# WIFI.net
KiCad netlist of a schematic drawn in Altium Designer
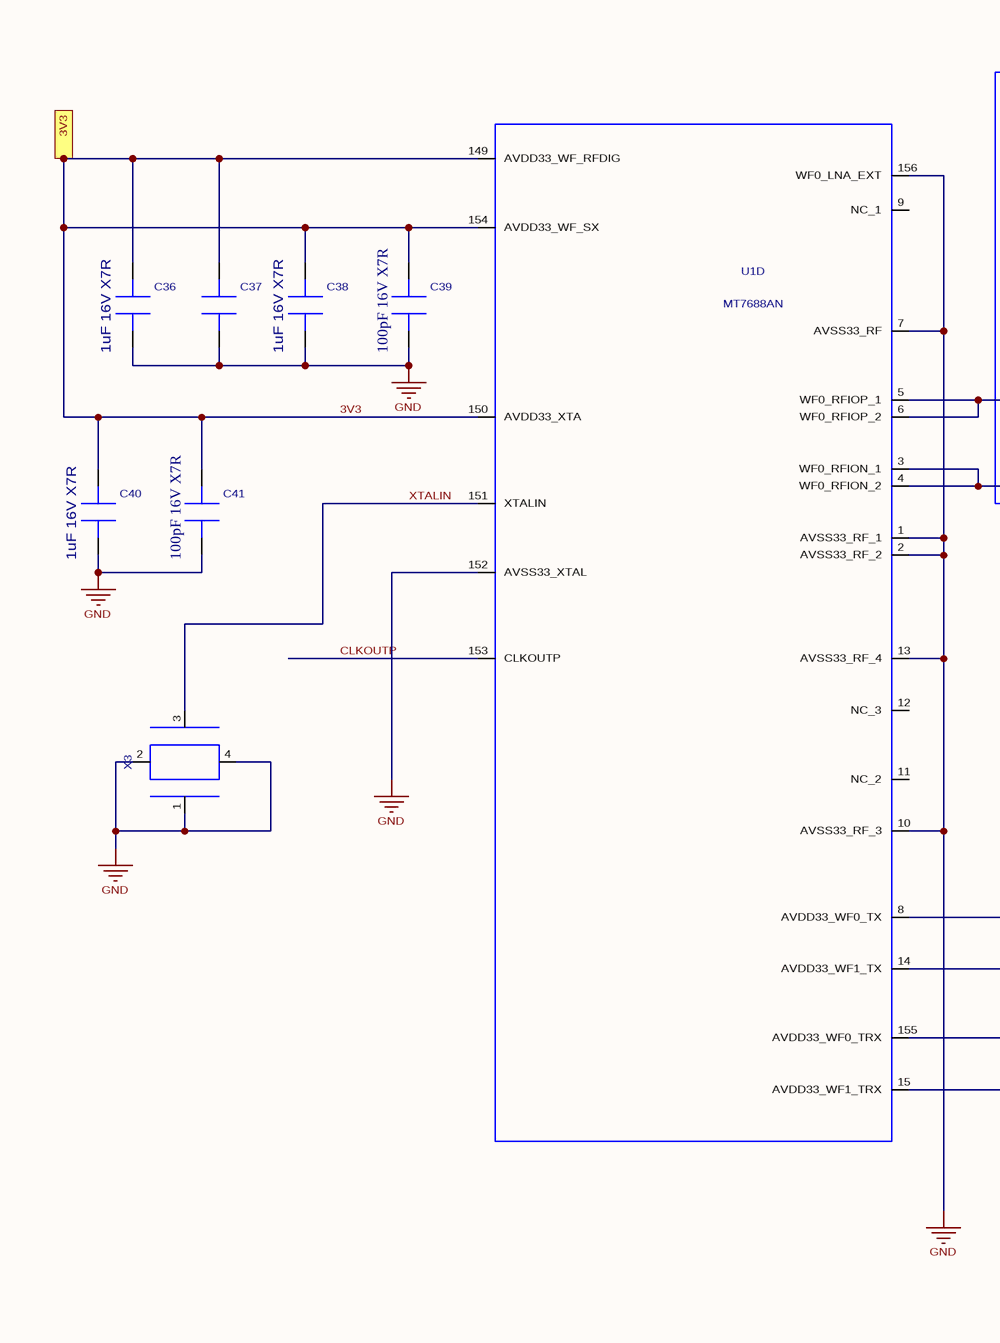
[diagram p0: WIFI.SchDoc, left]
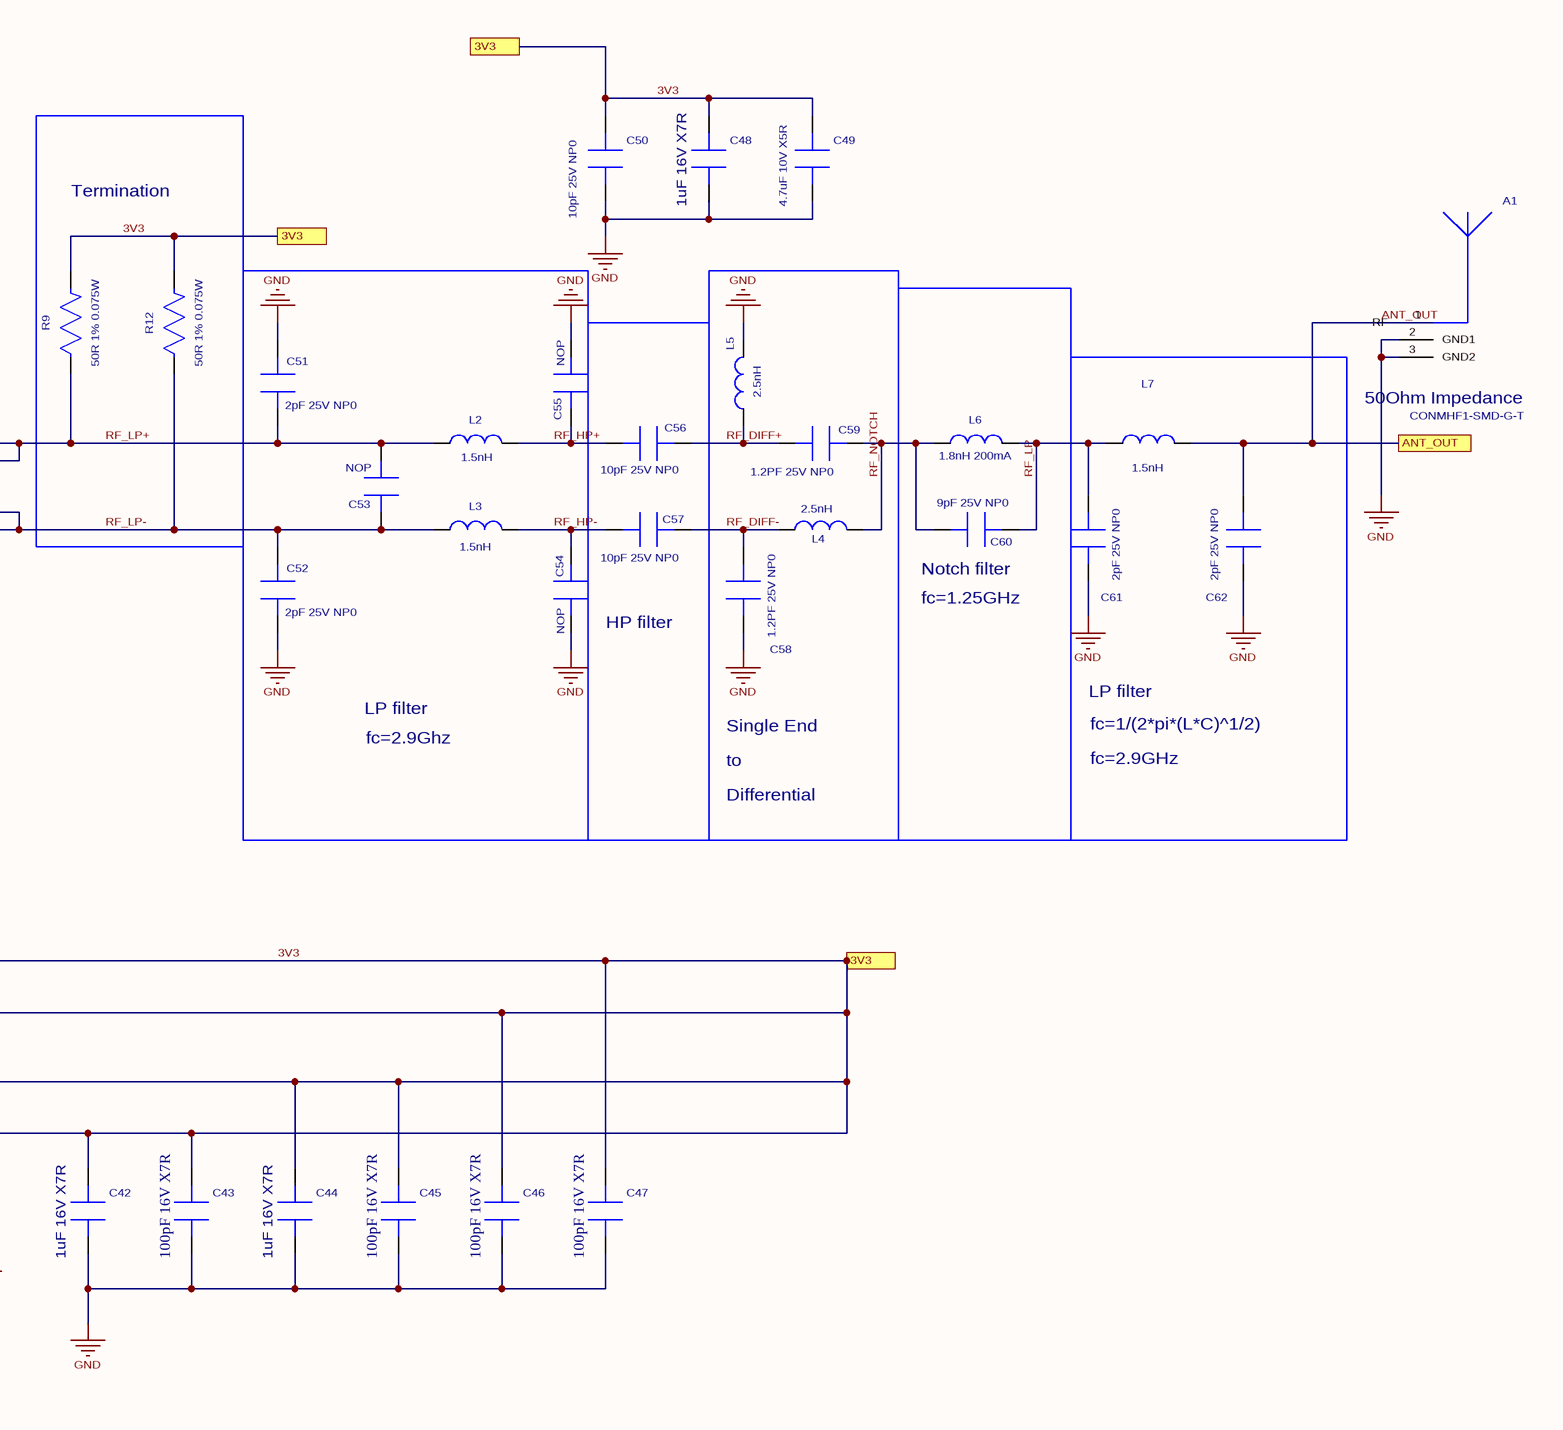
[diagram p1: WIFI.SchDoc, right]

(export (version "E")
  (design (tool "Eeschema 10.0.6"))
  (components
    (comp (ref "A1")
      (value "CONMHF1-SMD-G-T")
      (footprint "CONMHF1-SMD-G-T")
      (description "CONN UMC JACK STR SMD")
      (fields (field (name "MANUFACTURER") "Linx Technologies Inc."))
      (libsource (lib "*") (part "CONMHF1-SMD-G-T"))
    )
    (comp (ref "C36")
      (value "1uF 16V X7R")
      (footprint "C0402")
      (description "CAP CER 1UF 6.3V X7R 0402")
      (fields
        (field (name "PART NUMBER") "GRM155R70J105KA12D")
        (field (name "MANUFACTURER") "Murata Electronics")
      )
      (libsource (lib "NetworkModule") (part "CAP0402-105-6.3V-X7R"))
    )
    (comp (ref "C37")
      (value "CAP0201-101-16V-X7R")
      (footprint "C0201")
      (description "CAP CER 100PF 16V X7R 0201")
      (fields
        (field (name "PART NUMBER") "0201B101K160CT")
        (field (name "MANUFACTURER") "Walsin Technology Corporation")
      )
      (libsource (lib "NetworkModule") (part "CAP0201-101-16V-X7R"))
    )
    (comp (ref "C38")
      (value "1uF 16V X7R")
      (footprint "C0402")
      (description "CAP CER 1UF 6.3V X7R 0402")
      (fields
        (field (name "PART NUMBER") "GRM155R70J105KA12D")
        (field (name "MANUFACTURER") "Murata Electronics")
      )
      (libsource (lib "NetworkModule") (part "CAP0402-105-6.3V-X7R"))
    )
    (comp (ref "C39")
      (value "100pF 16V X7R")
      (footprint "C0201")
      (description "CAP CER 100PF 16V X7R 0201")
      (fields
        (field (name "PART NUMBER") "0201B101K160CT")
        (field (name "MANUFACTURER") "Walsin Technology Corporation")
      )
      (libsource (lib "NetworkModule") (part "CAP0201-101-16V-X7R"))
    )
    (comp (ref "C40")
      (value "1uF 16V X7R")
      (footprint "C0402")
      (description "CAP CER 1UF 6.3V X7R 0402")
      (fields
        (field (name "PART NUMBER") "GRM155R70J105KA12D")
        (field (name "MANUFACTURER") "Murata Electronics")
      )
      (libsource (lib "NetworkModule") (part "CAP0402-105-6.3V-X7R"))
    )
    (comp (ref "C41")
      (value "100pF 16V X7R")
      (footprint "C0201")
      (description "CAP CER 100PF 16V X7R 0201")
      (fields
        (field (name "PART NUMBER") "0201B101K160CT")
        (field (name "MANUFACTURER") "Walsin Technology Corporation")
      )
      (libsource (lib "NetworkModule") (part "CAP0201-101-16V-X7R"))
    )
    (comp (ref "C42")
      (value "1uF 16V X7R")
      (footprint "C0402")
      (description "CAP CER 1UF 6.3V X7R 0402")
      (fields
        (field (name "PART NUMBER") "GRM155R70J105KA12D")
        (field (name "MANUFACTURER") "Murata Electronics")
      )
      (libsource (lib "NetworkModule") (part "CAP0402-105-6.3V-X7R"))
    )
    (comp (ref "C43")
      (value "100pF 16V X7R")
      (footprint "C0201")
      (description "CAP CER 100PF 16V X7R 0201")
      (fields
        (field (name "PART NUMBER") "0201B101K160CT")
        (field (name "MANUFACTURER") "Walsin Technology Corporation")
      )
      (libsource (lib "NetworkModule") (part "CAP0201-101-16V-X7R"))
    )
    (comp (ref "C44")
      (value "1uF 16V X7R")
      (footprint "C0402")
      (description "CAP CER 1UF 6.3V X7R 0402")
      (fields
        (field (name "PART NUMBER") "GRM155R70J105KA12D")
        (field (name "MANUFACTURER") "Murata Electronics")
      )
      (libsource (lib "NetworkModule") (part "CAP0402-105-6.3V-X7R"))
    )
    (comp (ref "C45")
      (value "100pF 16V X7R")
      (footprint "C0201")
      (description "CAP CER 100PF 16V X7R 0201")
      (fields
        (field (name "PART NUMBER") "0201B101K160CT")
        (field (name "MANUFACTURER") "Walsin Technology Corporation")
      )
      (libsource (lib "NetworkModule") (part "CAP0201-101-16V-X7R"))
    )
    (comp (ref "C46")
      (value "100pF 16V X7R")
      (footprint "C0201")
      (description "CAP CER 100PF 16V X7R 0201")
      (fields
        (field (name "PART NUMBER") "0201B101K160CT")
        (field (name "MANUFACTURER") "Walsin Technology Corporation")
      )
      (libsource (lib "NetworkModule") (part "CAP0201-101-16V-X7R"))
    )
    (comp (ref "C47")
      (value "100pF 16V X7R")
      (footprint "C0201")
      (description "CAP CER 100PF 16V X7R 0201")
      (fields
        (field (name "PART NUMBER") "0201B101K160CT")
        (field (name "MANUFACTURER") "Walsin Technology Corporation")
      )
      (libsource (lib "NetworkModule") (part "CAP0201-101-16V-X7R"))
    )
    (comp (ref "C48")
      (value "1uF 16V X7R")
      (footprint "C0402")
      (description "CAP CER 1UF 6.3V X7R 0402")
      (fields
        (field (name "PART NUMBER") "GRM155R70J105KA12D")
        (field (name "MANUFACTURER") "Murata Electronics")
      )
      (libsource (lib "NetworkModule") (part "CAP0402-105-6.3V-X7R"))
    )
    (comp (ref "C49")
      (value "4.7uF 10V X5R")
      (footprint "C0402")
      (description "CAP CER 4.7UF 10V X5R 0402")
      (fields
        (field (name "PART NUMBER") "CL05A475MP5NRNC")
        (field (name "MANUFACTURER") "Samsung Electro-Mechanics")
      )
      (libsource (lib "NetworkModule") (part "CAP0402-475-10V-X5R"))
    )
    (comp (ref "C50")
      (value "10pF 25V NP0")
      (footprint "C0201")
      (description "CAP CER 10PF 25V C0G/NP0 0201")
      (fields
        (field (name "PART NUMBER") "0201N100J250CT")
        (field (name "MANUFACTURER") "Walsin Technology Corporation")
      )
      (libsource (lib "NetworkModule") (part "CAP0201-100-25V-NP0"))
    )
    (comp (ref "C51")
      (value "2pF 25V NP0")
      (footprint "C0201")
      (description "CAP CER 2PF 25V C0G/NP0 0201")
      (fields
        (field (name "PART NUMBER") "CL03C020BA3GNNC")
        (field (name "MANUFACTURER") "Samsung Electro-Mechanics")
      )
      (libsource (lib "NetworkModule") (part "CAP0201-020-25V-NP0"))
    )
    (comp (ref "C52")
      (value "2pF 25V NP0")
      (footprint "C0201")
      (description "CAP CER 2PF 25V C0G/NP0 0201")
      (fields
        (field (name "PART NUMBER") "CL03C020BA3GNNC")
        (field (name "MANUFACTURER") "Samsung Electro-Mechanics")
      )
      (libsource (lib "NetworkModule") (part "CAP0201-020-25V-NP0"))
    )
    (comp (ref "C53")
      (value "NOP")
      (footprint "C0201_NOP")
      (fields (field (name "Comment") "CAP0201-NOP"))
      (libsource (lib "NetworkModule") (part "CAP0201-NOP"))
    )
    (comp (ref "C54")
      (value "NOP")
      (footprint "C0201_NOP")
      (fields (field (name "Comment") "CAP0201-NOP"))
      (libsource (lib "NetworkModule") (part "CAP0201-NOP"))
    )
    (comp (ref "C55")
      (value "NOP")
      (footprint "C0201_NOP")
      (fields (field (name "Comment") "CAP0201-NOP"))
      (libsource (lib "NetworkModule") (part "CAP0201-NOP"))
    )
    (comp (ref "C56")
      (value "10pF 25V NP0")
      (footprint "C0201")
      (description "CAP CER 10PF 25V C0G/NP0 0201")
      (fields
        (field (name "PART NUMBER") "0201N100J250CT")
        (field (name "MANUFACTURER") "Walsin Technology Corporation")
      )
      (libsource (lib "NetworkModule") (part "CAP0201-100-25V-NP0"))
    )
    (comp (ref "C57")
      (value "10pF 25V NP0")
      (footprint "C0201")
      (description "CAP CER 10PF 25V C0G/NP0 0201")
      (fields
        (field (name "PART NUMBER") "0201N100J250CT")
        (field (name "MANUFACTURER") "Walsin Technology Corporation")
      )
      (libsource (lib "NetworkModule") (part "CAP0201-100-25V-NP0"))
    )
    (comp (ref "C58")
      (value "1.2PF 25V NP0")
      (footprint "C0201")
      (description "CAP CER 1.2PF 25V C0G/NP0 0201")
      (fields
        (field (name "PART NUMBER") "GRM0335C1E1R2WA01D")
        (field (name "MANUFACTURER") "Murata Electronics")
      )
      (libsource (lib "NetworkModule") (part "CAP0201-1R2-25V-NP0"))
    )
    (comp (ref "C59")
      (value "1.2PF 25V NP0")
      (footprint "C0201")
      (description "CAP CER 1.2PF 25V C0G/NP0 0201")
      (fields
        (field (name "PART NUMBER") "GRM0335C1E1R2WA01D")
        (field (name "MANUFACTURER") "Murata Electronics")
      )
      (libsource (lib "NetworkModule") (part "CAP0201-1R2-25V-NP0"))
    )
    (comp (ref "C60")
      (value "9pF 25V NP0")
      (footprint "C0201")
      (description "CAP CER 9PF 25V C0G 0201")
      (fields
        (field (name "PART NUMBER") "CGA1A2C0G1E090D030BA")
        (field (name "MANUFACTURER") "TDK Corporation")
      )
      (libsource (lib "NetworkModule") (part "CAP0201-090-100V-NP0"))
    )
    (comp (ref "C61")
      (value "2pF 25V NP0")
      (footprint "C0201")
      (description "CAP CER 2PF 25V C0G/NP0 0201")
      (fields
        (field (name "PART NUMBER") "CL03C020BA3GNNC")
        (field (name "MANUFACTURER") "Samsung Electro-Mechanics")
      )
      (libsource (lib "NetworkModule") (part "CAP0201-020-25V-NP0"))
    )
    (comp (ref "C62")
      (value "2pF 25V NP0")
      (footprint "C0201")
      (description "CAP CER 2PF 25V C0G/NP0 0201")
      (fields
        (field (name "PART NUMBER") "CL03C020BA3GNNC")
        (field (name "MANUFACTURER") "Samsung Electro-Mechanics")
      )
      (libsource (lib "NetworkModule") (part "CAP0201-020-25V-NP0"))
    )
    (comp (ref "L2")
      (value "1.5nH")
      (footprint "L0201")
      (description "INDUCTOR FIXED 1.5NH 0201")
      (fields
        (field (name "PART NUMBER") "WLCM0603TGB1N5TB")
        (field (name "MANUFACTURER") "Walsin Technology Corporation")
      )
      (libsource (lib "NetworkModule") (part "IND0201_1.5N_600MA"))
    )
    (comp (ref "L3")
      (value "1.5nH")
      (footprint "L0201")
      (description "INDUCTOR FIXED 1.5NH 0201")
      (fields
        (field (name "PART NUMBER") "WLCM0603TGB1N5TB")
        (field (name "MANUFACTURER") "Walsin Technology Corporation")
      )
      (libsource (lib "NetworkModule") (part "IND0201_1.5N_600MA"))
    )
    (comp (ref "L4")
      (value "2.5nH")
      (footprint "L0201")
      (description "FIXED IND 2.5NH 500MA 200MOHM SM")
      (fields
        (field (name "PART NUMBER") "LQP03TN2N5B02D")
        (field (name "MANUFACTURER") "Murata Electronics")
      )
      (libsource (lib "NetworkModule") (part "IND0201_2.5N_500MA"))
    )
    (comp (ref "L5")
      (value "2.5nH")
      (footprint "L0201")
      (description "FIXED IND 2.5NH 500MA 200MOHM SM")
      (fields
        (field (name "PART NUMBER") "LQP03TN2N5B02D")
        (field (name "MANUFACTURER") "Murata Electronics")
      )
      (libsource (lib "NetworkModule") (part "IND0201_2.5N_500MA"))
    )
    (comp (ref "L6")
      (value "1.8nH 200mA")
      (footprint "L0201")
      (description "FIXED IND 1.8NH 200MA 550MOHM SM")
      (fields
        (field (name "PART NUMBER") "1-2176075-8")
        (field (name "MANUFACTURER") "TE Connectivity Passive Product")
      )
      (libsource (lib "NetworkModule") (part "IND0201_1.8N_200MA"))
    )
    (comp (ref "L7")
      (value "1.5nH")
      (footprint "L0201")
      (description "INDUCTOR FIXED 1.5NH 0201")
      (fields
        (field (name "PART NUMBER") "WLCM0603TGB1N5TB")
        (field (name "MANUFACTURER") "Walsin Technology Corporation")
      )
      (libsource (lib "NetworkModule") (part "IND0201_1.5N_600MA"))
    )
    (comp (ref "R9")
      (value "50R 1% 0.075W")
      (footprint "R0201")
      (description "RES 50 OHM 0.1% 0.075W 0201")
      (fields (field (name "MANUFACTURER") "Vishay Dale") (field (name "PART NUMBER") "TNPW020150R0BEED"))
      (libsource (lib "NetworkModule") (part "RES0201-50R0"))
    )
    (comp (ref "R12")
      (value "50R 1% 0.075W")
      (footprint "R0201")
      (description "RES 50 OHM 0.1% 0.075W 0201")
      (fields (field (name "MANUFACTURER") "Vishay Dale") (field (name "PART NUMBER") "TNPW020150R0BEED"))
      (libsource (lib "NetworkModule") (part "RES0201-50R0"))
    )
    (comp (ref "U1")
      (value "MT7688AN")
      (footprint "DR-QFN-128")
      (description "580Mhz 32bits Networking Processor")
      (fields (field (name "MANUFACTURER") "MediaTek Inc"))
      (libsource (lib "*") (part "MT7688AN"))
    )
    (comp (ref "X3")
      (value "R2520-40.000-12-F-1010-TR-NS1")
      (footprint "R2520-40.000-12-F-1010-TR-NS1")
      (description "CRYSTAL 40.0000MHZ 12PF SMD")
      (fields (field (name "MANUFACTURER") "Raltron Electronics"))
      (libsource (lib "*") (part "R2520-40.000-12-F-1010-TR-NS1"))
    )
  )
  (nets
    (net (code "1") (name "/3V3") (class "Default")
      (node (ref "C36") (pin "1") (pinfunction "1_1") (pintype "passive"))
      (node (ref "C37") (pin "1") (pinfunction "1_1") (pintype "passive"))
      (node (ref "C38") (pin "1") (pinfunction "1_1") (pintype "passive"))
      (node (ref "C39") (pin "1") (pinfunction "1_1") (pintype "passive"))
      (node (ref "C40") (pin "1") (pinfunction "1_1") (pintype "passive"))
      (node (ref "C41") (pin "1") (pinfunction "1_1") (pintype "passive"))
      (node (ref "C42") (pin "1") (pinfunction "1_1") (pintype "passive"))
      (node (ref "C43") (pin "1") (pinfunction "1_1") (pintype "passive"))
      (node (ref "C44") (pin "1") (pinfunction "1_1") (pintype "passive"))
      (node (ref "C45") (pin "1") (pinfunction "1_1") (pintype "passive"))
      (node (ref "C46") (pin "1") (pinfunction "1_1") (pintype "passive"))
      (node (ref "C47") (pin "1") (pinfunction "1_1") (pintype "passive"))
      (node (ref "C48") (pin "1") (pinfunction "1_1") (pintype "passive"))
      (node (ref "C49") (pin "1") (pinfunction "1_1") (pintype "passive"))
      (node (ref "C50") (pin "1") (pinfunction "1_1") (pintype "passive"))
      (node (ref "R12") (pin "2") (pinfunction "2_2") (pintype "passive"))
      (node (ref "R9") (pin "2") (pinfunction "2_2") (pintype "passive"))
      (node (ref "U1") (pin "14") (pinfunction "AVDD33_WF1_TX_14") (pintype "passive"))
      (node (ref "U1") (pin "149") (pinfunction "AVDD33_WF_RFDIG_149") (pintype "passive"))
      (node (ref "U1") (pin "15") (pinfunction "AVDD33_WF1_TRX_15") (pintype "passive"))
      (node (ref "U1") (pin "150") (pinfunction "AVDD33_XTA_150") (pintype "passive"))
      (node (ref "U1") (pin "154") (pinfunction "AVDD33_WF_SX_154") (pintype "passive"))
      (node (ref "U1") (pin "155") (pinfunction "AVDD33_WF0_TRX_155") (pintype "passive"))
      (node (ref "U1") (pin "8") (pinfunction "AVDD33_WF0_TX_8") (pintype "passive"))
    )
    (net (code "2") (name "/ANT_OUT") (class "Default")
      (node (ref "A1") (pin "1") (pinfunction "RF_1") (pintype "passive"))
      (node (ref "C62") (pin "1") (pinfunction "1_1") (pintype "passive"))
      (node (ref "L7") (pin "2") (pinfunction "2_2") (pintype "passive"))
    )
    (net (code "3") (name "/CLKOUTP") (class "Default")
      (node (ref "U1") (pin "153") (pinfunction "CLKOUTP_153") (pintype "passive"))
    )
    (net (code "4") (name "/RF_DIFF+") (class "Default")
      (node (ref "C56") (pin "1") (pinfunction "1_1") (pintype "passive"))
      (node (ref "C59") (pin "2") (pinfunction "2_2") (pintype "passive"))
      (node (ref "L5") (pin "1") (pinfunction "1_1") (pintype "passive"))
    )
    (net (code "5") (name "/RF_DIFF-") (class "Default")
      (node (ref "C57") (pin "1") (pinfunction "1_1") (pintype "passive"))
      (node (ref "C58") (pin "1") (pinfunction "1_1") (pintype "passive"))
      (node (ref "L4") (pin "1") (pinfunction "1_1") (pintype "passive"))
    )
    (net (code "6") (name "/RF_HP+") (class "Default")
      (node (ref "C55") (pin "1") (pinfunction "1_1") (pintype "passive"))
      (node (ref "C56") (pin "2") (pinfunction "2_2") (pintype "passive"))
      (node (ref "L2") (pin "2") (pinfunction "2_2") (pintype "passive"))
    )
    (net (code "7") (name "/RF_HP-") (class "Default")
      (node (ref "C54") (pin "1") (pinfunction "1_1") (pintype "passive"))
      (node (ref "C57") (pin "2") (pinfunction "2_2") (pintype "passive"))
      (node (ref "L3") (pin "2") (pinfunction "2_2") (pintype "passive"))
    )
    (net (code "8") (name "/RF_LP") (class "Default")
      (node (ref "C60") (pin "1") (pinfunction "1_1") (pintype "passive"))
      (node (ref "C61") (pin "1") (pinfunction "1_1") (pintype "passive"))
      (node (ref "L6") (pin "2") (pinfunction "2_2") (pintype "passive"))
      (node (ref "L7") (pin "1") (pinfunction "1_1") (pintype "passive"))
    )
    (net (code "9") (name "/RF_LP+") (class "Default")
      (node (ref "C51") (pin "2") (pinfunction "2_2") (pintype "passive"))
      (node (ref "C53") (pin "1") (pinfunction "1_1") (pintype "passive"))
      (node (ref "L2") (pin "1") (pinfunction "1_1") (pintype "passive"))
      (node (ref "R9") (pin "1") (pinfunction "1_1") (pintype "passive"))
      (node (ref "U1") (pin "5") (pinfunction "WF0_RFIOP_1_5") (pintype "passive"))
      (node (ref "U1") (pin "6") (pinfunction "WF0_RFIOP_2_6") (pintype "passive"))
    )
    (net (code "10") (name "/RF_LP-") (class "Default")
      (node (ref "C52") (pin "1") (pinfunction "1_1") (pintype "passive"))
      (node (ref "C53") (pin "2") (pinfunction "2_2") (pintype "passive"))
      (node (ref "L3") (pin "1") (pinfunction "1_1") (pintype "passive"))
      (node (ref "R12") (pin "1") (pinfunction "1_1") (pintype "passive"))
      (node (ref "U1") (pin "3") (pinfunction "WF0_RFION_1_3") (pintype "passive"))
      (node (ref "U1") (pin "4") (pinfunction "WF0_RFION_2_4") (pintype "passive"))
    )
    (net (code "11") (name "/RF_NOTCH") (class "Default")
      (node (ref "C59") (pin "1") (pinfunction "1_1") (pintype "passive"))
      (node (ref "C60") (pin "2") (pinfunction "2_2") (pintype "passive"))
      (node (ref "L4") (pin "2") (pinfunction "2_2") (pintype "passive"))
      (node (ref "L6") (pin "1") (pinfunction "1_1") (pintype "passive"))
    )
    (net (code "12") (name "/XTALIN") (class "Default")
      (node (ref "U1") (pin "151") (pinfunction "XTALIN_151") (pintype "passive"))
      (node (ref "X3") (pin "3") (pinfunction "3_3") (pintype "passive"))
    )
    (net (code "13") (name "GND") (class "Default")
      (node (ref "A1") (pin "2") (pinfunction "GND1_2") (pintype "passive"))
      (node (ref "A1") (pin "3") (pinfunction "GND2_3") (pintype "passive"))
      (node (ref "C36") (pin "2") (pinfunction "2_2") (pintype "passive"))
      (node (ref "C37") (pin "2") (pinfunction "2_2") (pintype "passive"))
      (node (ref "C38") (pin "2") (pinfunction "2_2") (pintype "passive"))
      (node (ref "C39") (pin "2") (pinfunction "2_2") (pintype "passive"))
      (node (ref "C40") (pin "2") (pinfunction "2_2") (pintype "passive"))
      (node (ref "C41") (pin "2") (pinfunction "2_2") (pintype "passive"))
      (node (ref "C42") (pin "2") (pinfunction "2_2") (pintype "passive"))
      (node (ref "C43") (pin "2") (pinfunction "2_2") (pintype "passive"))
      (node (ref "C44") (pin "2") (pinfunction "2_2") (pintype "passive"))
      (node (ref "C45") (pin "2") (pinfunction "2_2") (pintype "passive"))
      (node (ref "C46") (pin "2") (pinfunction "2_2") (pintype "passive"))
      (node (ref "C47") (pin "2") (pinfunction "2_2") (pintype "passive"))
      (node (ref "C48") (pin "2") (pinfunction "2_2") (pintype "passive"))
      (node (ref "C49") (pin "2") (pinfunction "2_2") (pintype "passive"))
      (node (ref "C50") (pin "2") (pinfunction "2_2") (pintype "passive"))
      (node (ref "C51") (pin "1") (pinfunction "1_1") (pintype "passive"))
      (node (ref "C52") (pin "2") (pinfunction "2_2") (pintype "passive"))
      (node (ref "C54") (pin "2") (pinfunction "2_2") (pintype "passive"))
      (node (ref "C55") (pin "2") (pinfunction "2_2") (pintype "passive"))
      (node (ref "C58") (pin "2") (pinfunction "2_2") (pintype "passive"))
      (node (ref "C61") (pin "2") (pinfunction "2_2") (pintype "passive"))
      (node (ref "C62") (pin "2") (pinfunction "2_2") (pintype "passive"))
      (node (ref "L5") (pin "2") (pinfunction "2_2") (pintype "passive"))
      (node (ref "U1") (pin "1") (pinfunction "AVSS33_RF_1_1") (pintype "passive"))
      (node (ref "U1") (pin "10") (pinfunction "AVSS33_RF_3_10") (pintype "passive"))
      (node (ref "U1") (pin "13") (pinfunction "AVSS33_RF_4_13") (pintype "passive"))
      (node (ref "U1") (pin "152") (pinfunction "AVSS33_XTAL_152") (pintype "passive"))
      (node (ref "U1") (pin "156") (pinfunction "WF0_LNA_EXT_156") (pintype "passive"))
      (node (ref "U1") (pin "2") (pinfunction "AVSS33_RF_2_2") (pintype "passive"))
      (node (ref "U1") (pin "7") (pinfunction "AVSS33_RF_7") (pintype "passive"))
      (node (ref "X3") (pin "1") (pinfunction "1_1") (pintype "passive"))
      (node (ref "X3") (pin "2") (pinfunction "GND1_2") (pintype "passive"))
      (node (ref "X3") (pin "4") (pinfunction "GND2_4") (pintype "passive"))
    )
    (net (code "14") (name "unconnected-(U1D-NC_1-Pad9)") (class "Default")
      (node (ref "U1") (pin "9") (pinfunction "NC_1_9") (pintype "passive"))
    )
    (net (code "15") (name "unconnected-(U1D-NC_2-Pad11)") (class "Default")
      (node (ref "U1") (pin "11") (pinfunction "NC_2_11") (pintype "passive"))
    )
    (net (code "16") (name "unconnected-(U1D-NC_3-Pad12)") (class "Default")
      (node (ref "U1") (pin "12") (pinfunction "NC_3_12") (pintype "passive"))
    )
  )
)
